# EQ_C.net
KiCad netlist of a schematic drawn in Altium Designer
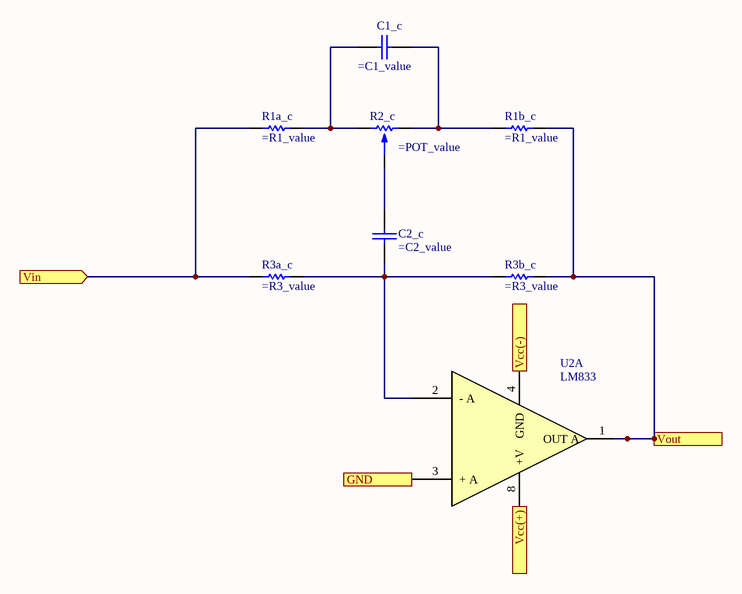
[diagram p0: EQ_C.SchDoc]

(export (version "E")
  (design (tool "Eeschema 10.0.6"))
  (components
    (comp (ref "C1_c") (value "~") (footprint "CAP200") (libsource (lib "LIBEBAL") (part "CAP")))
    (comp (ref "C2_c") (value "~") (footprint "CAP200") (libsource (lib "LIBEBAL") (part "CAP")))
    (comp (ref "R1a_c") (value "~") (footprint "0805") (libsource (lib "LIBEBAL") (part "RES")))
    (comp (ref "R1b_c") (value "~") (footprint "0805") (libsource (lib "LIBEBAL") (part "RES")))
    (comp (ref "R2_c")
      (value "~")
      (footprint "POTENCIOMETRO")
      (libsource (lib "LIBEBAL") (part "POTENCIOMETRO"))
    )
    (comp (ref "R3a_c") (value "~") (footprint "0805") (libsource (lib "LIBEBAL") (part "RES")))
    (comp (ref "R3b_c") (value "~") (footprint "0805") (libsource (lib "LIBEBAL") (part "RES")))
    (comp (ref "U2")
      (value "LM833")
      (footprint "DIP8")
      (description "Dual Audio Operational Amplifier")
      (libsource (lib "LIBEBAL") (part "LM833"))
    )
  )
  (nets
    (net (code "1") (name "/GND") (class "Default")
      (node (ref "U2") (pin "3") (pinfunction "+_A_3") (pintype "passive"))
    )
    (net (code "2") (name "/Vcc(+)") (class "Default")
      (node (ref "U2") (pin "8") (pinfunction "+V_8") (pintype "passive"))
    )
    (net (code "4") (name "/Vcc(-)") (class "Default")
      (node (ref "U2") (pin "4") (pinfunction "GND_4") (pintype "passive"))
    )
    (net (code "5") (name "/Vin") (class "Default")
      (node (ref "R1a_c") (pin "1") (pinfunction "1_1") (pintype "passive"))
      (node (ref "R3a_c") (pin "1") (pinfunction "1_1") (pintype "passive"))
    )
    (net (code "6") (name "/Vout") (class "Default")
      (node (ref "R1b_c") (pin "2") (pinfunction "2_2") (pintype "passive"))
      (node (ref "R3b_c") (pin "2") (pinfunction "2_2") (pintype "passive"))
      (node (ref "U2") (pin "1") (pinfunction "OUT_A_1") (pintype "passive"))
    )
    (net (code "7") (name "Net-(C1_c-Pad1)") (class "Default")
      (node (ref "C1_c") (pin "1") (pinfunction "1_1") (pintype "passive"))
      (node (ref "R1a_c") (pin "2") (pinfunction "2_2") (pintype "passive"))
      (node (ref "R2_c") (pin "3") (pinfunction "3_3") (pintype "passive"))
    )
    (net (code "8") (name "Net-(C1_c-Pad2)") (class "Default")
      (node (ref "C1_c") (pin "2") (pinfunction "2_2") (pintype "passive"))
      (node (ref "R1b_c") (pin "1") (pinfunction "1_1") (pintype "passive"))
      (node (ref "R2_c") (pin "1") (pinfunction "1_1") (pintype "passive"))
    )
    (net (code "9") (name "Net-(C2_c-Pad1)") (class "Default")
      (node (ref "C2_c") (pin "1") (pinfunction "1_1") (pintype "passive"))
      (node (ref "R2_c") (pin "2") (pinfunction "2_2") (pintype "passive"))
    )
    (net (code "10") (name "Net-(U2A--_A)") (class "Default")
      (node (ref "C2_c") (pin "2") (pinfunction "2_2") (pintype "passive"))
      (node (ref "R3a_c") (pin "2") (pinfunction "2_2") (pintype "passive"))
      (node (ref "R3b_c") (pin "1") (pinfunction "1_1") (pintype "passive"))
      (node (ref "U2") (pin "2") (pinfunction "-_A_2") (pintype "passive"))
    )
  )
)
